# USB_BREAKOUTS_CCU_HAS.net
KiCad netlist of a schematic drawn in Altium Designer
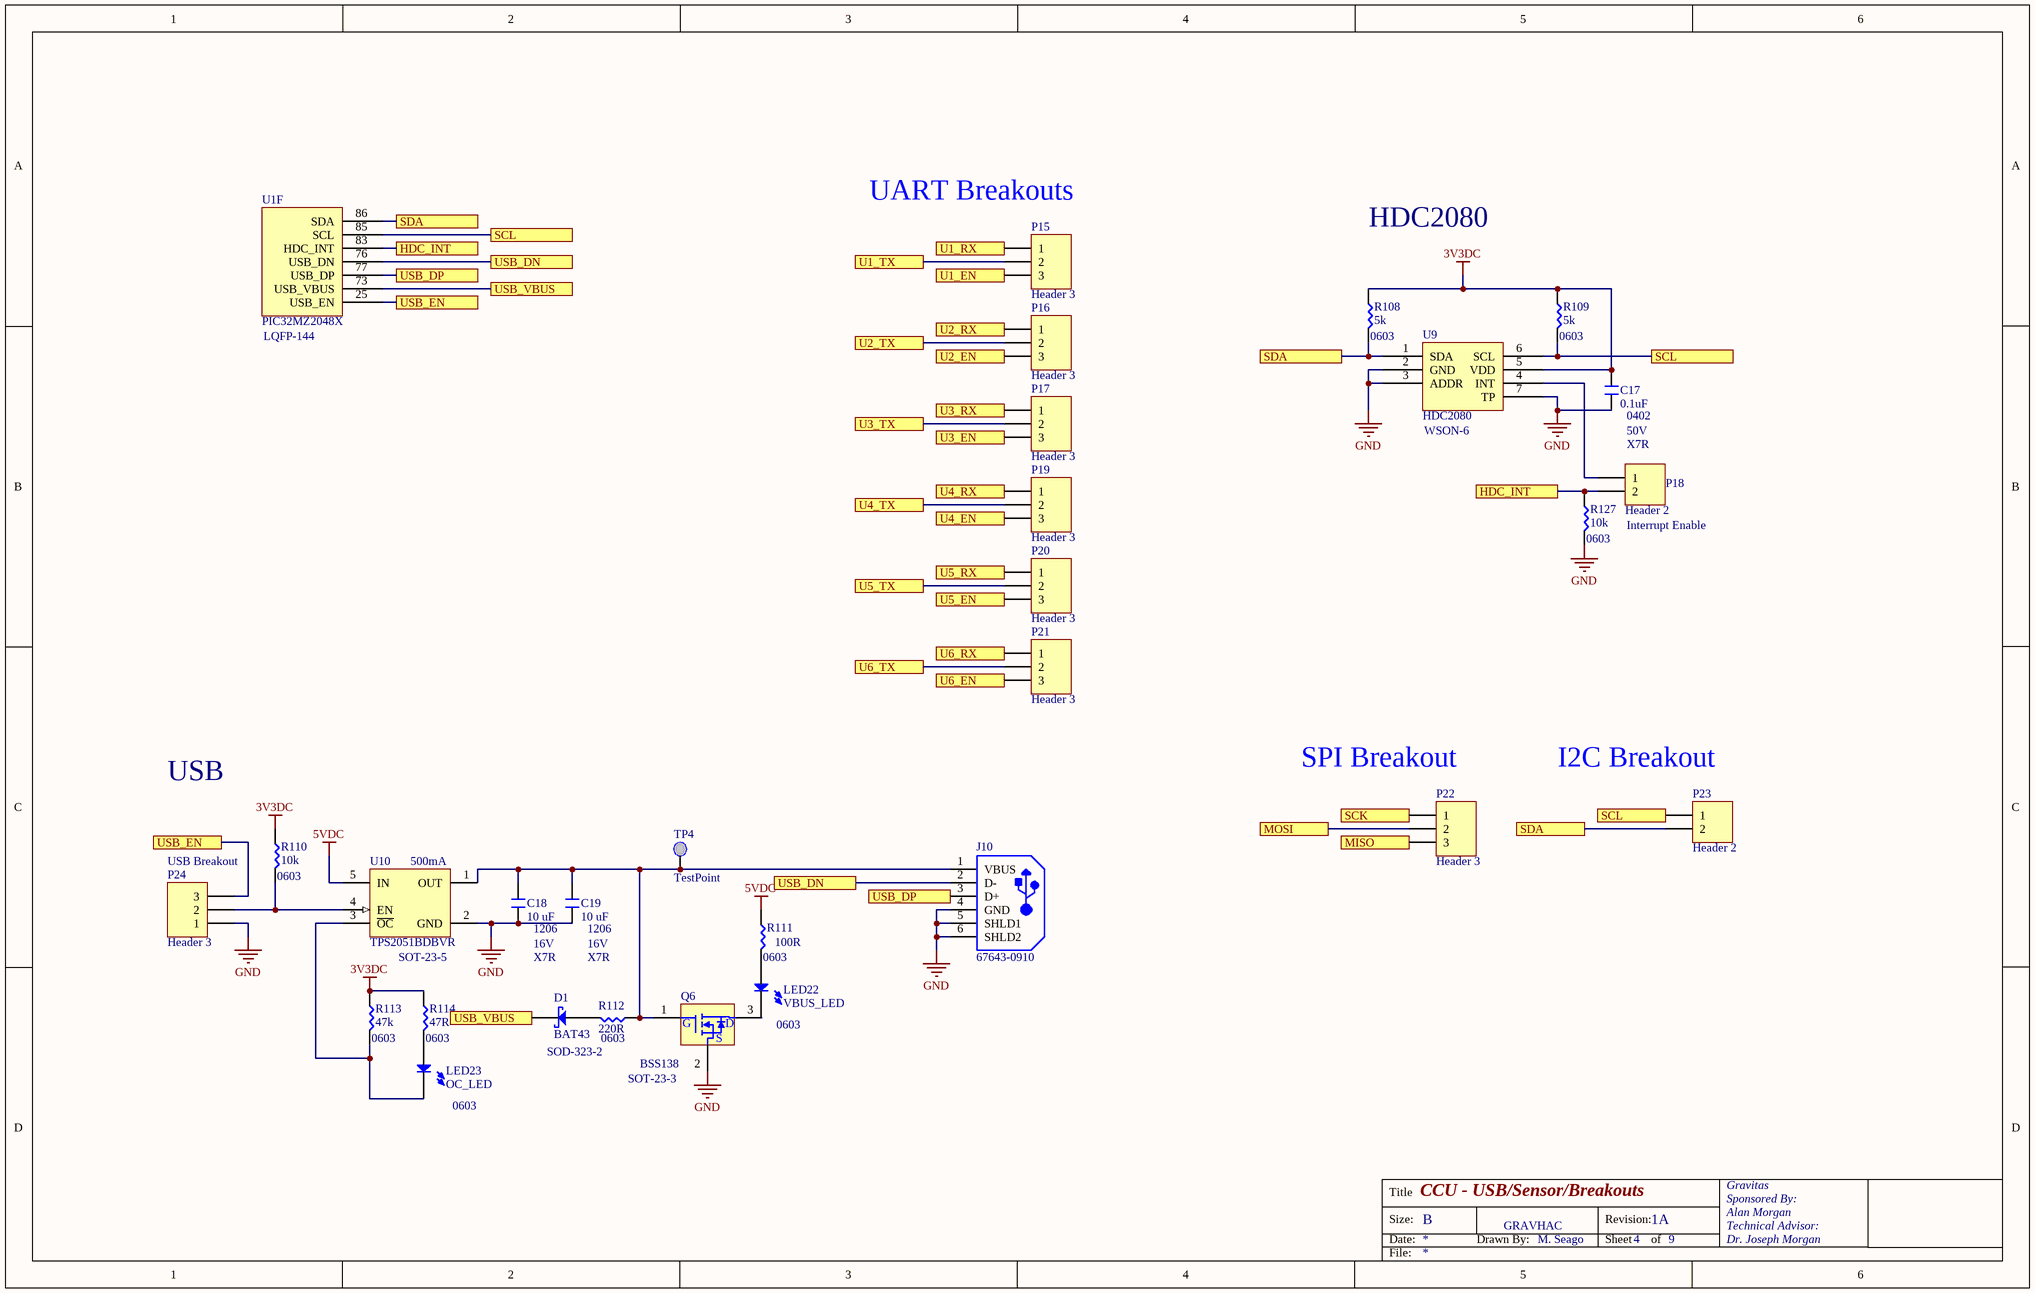
[diagram p0: USB_BREAKOUTS_CCU_HAS.SchDoc]

(export (version "E")
  (design (tool "Eeschema 10.0.6"))
  (components
    (comp (ref "C17")
      (value "0.1uF")
      (footprint "NonPolar-0402")
      (libsource (lib "GravLib") (part "Cap - 0402"))
    )
    (comp (ref "C18")
      (value "10 uF")
      (footprint "NONPOLAR-1206")
      (description "CGA5L1X7R1E106K160AE")
      (libsource (lib "GravLib") (part "Cap - 1206"))
    )
    (comp (ref "C19")
      (value "10 uF")
      (footprint "NONPOLAR-1206")
      (description "CGA5L1X7R1E106K160AE")
      (libsource (lib "GravLib") (part "Cap - 1206"))
    )
    (comp (ref "D1")
      (value "BAT43")
      (footprint "BAT43WS-E3-08")
      (description "BAT43WS-E3-08")
      (libsource (lib "GravLib") (part "BAT43"))
    )
    (comp (ref "J10")
      (value "67643-0910")
      (footprint "TE-292303-1_V")
      (fields (field (name "MANUFACTURER") "TE Connectivity"))
      (libsource (lib "Altium Content Vault") (part "USB-4-2SHLD"))
    )
    (comp (ref "LED22")
      (value "VBUS_LED")
      (footprint "LED-0603")
      (libsource (lib "GravLib") (part "LED-0603"))
    )
    (comp (ref "LED23") (value "OC_LED") (footprint "LED-0603") (libsource (lib "GravLib") (part "LED-0603")))
    (comp (ref "P15")
      (value "Header 3")
      (footprint "HDR1X3")
      (description "Header, 3-Pin")
      (fields (field (name "PUBLISHER") "Altium Limited"))
      (libsource (lib "Miscellaneous Connectors") (part "Header 3"))
    )
    (comp (ref "P16")
      (value "Header 3")
      (footprint "HDR1X3")
      (description "Header, 3-Pin")
      (fields (field (name "PUBLISHER") "Altium Limited"))
      (libsource (lib "Miscellaneous Connectors") (part "Header 3"))
    )
    (comp (ref "P17")
      (value "Header 3")
      (footprint "HDR1X3")
      (description "Header, 3-Pin")
      (fields (field (name "PUBLISHER") "Altium Limited"))
      (libsource (lib "Miscellaneous Connectors") (part "Header 3"))
    )
    (comp (ref "P18")
      (value "Header 2")
      (footprint "HDR1X2")
      (description "Header, 2-Pin")
      (fields (field (name "PUBLISHER") "Altium Limited"))
      (libsource (lib "Miscellaneous Connectors") (part "Header 2"))
    )
    (comp (ref "P19")
      (value "Header 3")
      (footprint "HDR1X3")
      (description "Header, 3-Pin")
      (fields (field (name "PUBLISHER") "Altium Limited"))
      (libsource (lib "Miscellaneous Connectors") (part "Header 3"))
    )
    (comp (ref "P20")
      (value "Header 3")
      (footprint "HDR1X3")
      (description "Header, 3-Pin")
      (fields (field (name "PUBLISHER") "Altium Limited"))
      (libsource (lib "Miscellaneous Connectors") (part "Header 3"))
    )
    (comp (ref "P21")
      (value "Header 3")
      (footprint "HDR1X3")
      (description "Header, 3-Pin")
      (fields (field (name "PUBLISHER") "Altium Limited"))
      (libsource (lib "Miscellaneous Connectors") (part "Header 3"))
    )
    (comp (ref "P22")
      (value "Header 3")
      (footprint "HDR1X3")
      (description "Header, 3-Pin")
      (fields (field (name "PUBLISHER") "Altium Limited"))
      (libsource (lib "Miscellaneous Connectors") (part "Header 3"))
    )
    (comp (ref "P23")
      (value "Header 2")
      (footprint "HDR1X2")
      (description "Header, 2-Pin")
      (fields (field (name "PUBLISHER") "Altium Limited"))
      (libsource (lib "Miscellaneous Connectors") (part "Header 2"))
    )
    (comp (ref "P24")
      (value "Header 3")
      (footprint "HDR1X3")
      (description "Header, 3-Pin")
      (fields (field (name "PUBLISHER") "Altium Limited"))
      (libsource (lib "") (part "Header 3_1"))
    )
    (comp (ref "Q6") (value "BSS138") (footprint "BSS138-SOT23") (libsource (lib "GravLib") (part "BSS138")))
    (comp (ref "R108")
      (value "5k")
      (footprint "NonPolar-0603")
      (libsource (lib "GravLib") (part "Res - 0603"))
    )
    (comp (ref "R109")
      (value "5k")
      (footprint "NonPolar-0603")
      (libsource (lib "GravLib") (part "Res - 0603"))
    )
    (comp (ref "R110")
      (value "10k")
      (footprint "NonPolar-0603")
      (libsource (lib "GravLib") (part "Res - 0603"))
    )
    (comp (ref "R111")
      (value "100R")
      (footprint "NonPolar-0603")
      (libsource (lib "GravLib") (part "Res - 0603"))
    )
    (comp (ref "R112")
      (value "220R")
      (footprint "NonPolar-0603")
      (libsource (lib "GravLib") (part "Res - 0603"))
    )
    (comp (ref "R113")
      (value "47k")
      (footprint "NonPolar-0603")
      (libsource (lib "GravLib") (part "Res - 0603"))
    )
    (comp (ref "R114")
      (value "47R")
      (footprint "NonPolar-0603")
      (libsource (lib "GravLib") (part "Res - 0603"))
    )
    (comp (ref "R127")
      (value "10k")
      (footprint "NonPolar-0603")
      (libsource (lib "GravLib") (part "Res - 0603"))
    )
    (comp (ref "TP4")
      (value "TestPoint")
      (footprint "TP - S2751-46R")
      (description "S2751-46R")
      (libsource (lib "GravLib") (part "TestPoint"))
    )
    (comp (ref "U1")
      (value "PIC32MZ2048X")
      (footprint "BIG_PIC32MZ")
      (libsource (lib "GravLib") (part "PIC32MZ2048X"))
    )
    (comp (ref "U9") (value "HDC2080") (footprint "HDC2080") (libsource (lib "GravLib") (part "HDC2080")))
    (comp (ref "U10")
      (value "TPS2051BDBVR")
      (footprint "DBV0005A_L")
      (fields (field (name "MANUFACTURER") "TexasInstruments"))
      (libsource (lib "Altium Content Vault") (part "TI-TPS2051BDBV5"))
    )
  )
  (nets
    (net (code "1") (name "/HDC_INT") (class "Default")
      (node (ref "P18") (pin "2") (pinfunction "2_2") (pintype "passive"))
      (node (ref "R127") (pin "2") (pinfunction "2_2") (pintype "passive"))
      (node (ref "U1") (pin "83") (pinfunction "HDC_INT_83") (pintype "passive"))
    )
    (net (code "2") (name "/MISO") (class "Default")
      (node (ref "P22") (pin "3") (pinfunction "3_3") (pintype "passive"))
    )
    (net (code "3") (name "/MOSI") (class "Default")
      (node (ref "P22") (pin "2") (pinfunction "2_2") (pintype "passive"))
    )
    (net (code "4") (name "/SCK") (class "Default")
      (node (ref "P22") (pin "1") (pinfunction "1_1") (pintype "passive"))
    )
    (net (code "5") (name "/SCL") (class "Default")
      (node (ref "P23") (pin "1") (pinfunction "1_1") (pintype "passive"))
      (node (ref "R109") (pin "1") (pinfunction "1_1") (pintype "passive"))
      (node (ref "U1") (pin "85") (pinfunction "SCL_85") (pintype "passive"))
      (node (ref "U9") (pin "6") (pinfunction "SCL_6") (pintype "passive"))
    )
    (net (code "6") (name "/SDA") (class "Default")
      (node (ref "P23") (pin "2") (pinfunction "2_2") (pintype "passive"))
      (node (ref "R108") (pin "1") (pinfunction "1_1") (pintype "passive"))
      (node (ref "U1") (pin "86") (pinfunction "SDA_86") (pintype "passive"))
      (node (ref "U9") (pin "1") (pinfunction "SDA_1") (pintype "passive"))
    )
    (net (code "7") (name "/U1_EN") (class "Default")
      (node (ref "P15") (pin "3") (pinfunction "3_3") (pintype "passive"))
    )
    (net (code "8") (name "/U1_RX") (class "Default")
      (node (ref "P15") (pin "1") (pinfunction "1_1") (pintype "passive"))
    )
    (net (code "9") (name "/U1_TX") (class "Default")
      (node (ref "P15") (pin "2") (pinfunction "2_2") (pintype "passive"))
    )
    (net (code "10") (name "/U2_EN") (class "Default")
      (node (ref "P16") (pin "3") (pinfunction "3_3") (pintype "passive"))
    )
    (net (code "11") (name "/U2_RX") (class "Default")
      (node (ref "P16") (pin "1") (pinfunction "1_1") (pintype "passive"))
    )
    (net (code "12") (name "/U2_TX") (class "Default")
      (node (ref "P16") (pin "2") (pinfunction "2_2") (pintype "passive"))
    )
    (net (code "13") (name "/U3_EN") (class "Default")
      (node (ref "P17") (pin "3") (pinfunction "3_3") (pintype "passive"))
    )
    (net (code "14") (name "/U3_RX") (class "Default")
      (node (ref "P17") (pin "1") (pinfunction "1_1") (pintype "passive"))
    )
    (net (code "15") (name "/U3_TX") (class "Default")
      (node (ref "P17") (pin "2") (pinfunction "2_2") (pintype "passive"))
    )
    (net (code "16") (name "/U4_EN") (class "Default")
      (node (ref "P19") (pin "3") (pinfunction "3_3") (pintype "passive"))
    )
    (net (code "17") (name "/U4_RX") (class "Default")
      (node (ref "P19") (pin "1") (pinfunction "1_1") (pintype "passive"))
    )
    (net (code "18") (name "/U4_TX") (class "Default")
      (node (ref "P19") (pin "2") (pinfunction "2_2") (pintype "passive"))
    )
    (net (code "19") (name "/U5_EN") (class "Default")
      (node (ref "P20") (pin "3") (pinfunction "3_3") (pintype "passive"))
    )
    (net (code "20") (name "/U5_RX") (class "Default")
      (node (ref "P20") (pin "1") (pinfunction "1_1") (pintype "passive"))
    )
    (net (code "21") (name "/U5_TX") (class "Default")
      (node (ref "P20") (pin "2") (pinfunction "2_2") (pintype "passive"))
    )
    (net (code "22") (name "/U6_EN") (class "Default")
      (node (ref "P21") (pin "3") (pinfunction "3_3") (pintype "passive"))
    )
    (net (code "23") (name "/U6_RX") (class "Default")
      (node (ref "P21") (pin "1") (pinfunction "1_1") (pintype "passive"))
    )
    (net (code "24") (name "/U6_TX") (class "Default")
      (node (ref "P21") (pin "2") (pinfunction "2_2") (pintype "passive"))
    )
    (net (code "25") (name "/USB_DN") (class "Default")
      (node (ref "J10") (pin "2") (pinfunction "D-_2") (pintype "passive"))
      (node (ref "U1") (pin "76") (pinfunction "USB_DN_76") (pintype "passive"))
    )
    (net (code "26") (name "/USB_DP") (class "Default")
      (node (ref "J10") (pin "3") (pinfunction "D+_3") (pintype "passive"))
      (node (ref "U1") (pin "77") (pinfunction "USB_DP_77") (pintype "passive"))
    )
    (net (code "27") (name "/USB_EN") (class "Default")
      (node (ref "P24") (pin "3") (pinfunction "3_3") (pintype "passive"))
      (node (ref "U1") (pin "25") (pinfunction "USB_EN_25") (pintype "passive"))
    )
    (net (code "28") (name "/USB_VBUS") (class "Default")
      (node (ref "D1") (pin "1") (pinfunction "1_1") (pintype "passive"))
      (node (ref "U1") (pin "73") (pinfunction "USB_VBUS_73") (pintype "passive"))
    )
    (net (code "29") (name "3V3DC") (class "Default")
      (node (ref "C17") (pin "2") (pinfunction "2_2") (pintype "passive"))
      (node (ref "R108") (pin "2") (pinfunction "2_2") (pintype "passive"))
      (node (ref "R109") (pin "2") (pinfunction "2_2") (pintype "passive"))
      (node (ref "R110") (pin "2") (pinfunction "2_2") (pintype "passive"))
      (node (ref "R113") (pin "2") (pinfunction "2_2") (pintype "passive"))
      (node (ref "R114") (pin "2") (pinfunction "2_2") (pintype "passive"))
      (node (ref "U9") (pin "5") (pinfunction "VDD_5") (pintype "passive"))
    )
    (net (code "30") (name "5VDC") (class "Default")
      (node (ref "R111") (pin "2") (pinfunction "2_2") (pintype "passive"))
      (node (ref "U10") (pin "5") (pinfunction "IN_5") (pintype "power_in"))
    )
    (net (code "31") (name "GND") (class "Default")
      (node (ref "C17") (pin "1") (pinfunction "1_1") (pintype "passive"))
      (node (ref "C18") (pin "1") (pinfunction "1_1") (pintype "passive"))
      (node (ref "C19") (pin "1") (pinfunction "1_1") (pintype "passive"))
      (node (ref "J10") (pin "4") (pinfunction "GND_4") (pintype "passive"))
      (node (ref "J10") (pin "5") (pinfunction "SHLD1_5") (pintype "passive"))
      (node (ref "J10") (pin "6") (pinfunction "SHLD2_6") (pintype "passive"))
      (node (ref "P24") (pin "1") (pinfunction "1_1") (pintype "passive"))
      (node (ref "Q6") (pin "2") (pinfunction "S_2") (pintype "passive"))
      (node (ref "R127") (pin "1") (pinfunction "1_1") (pintype "passive"))
      (node (ref "U10") (pin "2") (pinfunction "GND_2") (pintype "power_in"))
      (node (ref "U9") (pin "2") (pinfunction "GND_2") (pintype "passive"))
      (node (ref "U9") (pin "3") (pinfunction "ADDR_3") (pintype "passive"))
      (node (ref "U9") (pin "7") (pinfunction "TP_7") (pintype "passive"))
    )
    (net (code "32") (name "Net-(D1-Pad2)") (class "Default")
      (node (ref "D1") (pin "2") (pinfunction "2_2") (pintype "passive"))
      (node (ref "R112") (pin "1") (pinfunction "1_1") (pintype "passive"))
    )
    (net (code "33") (name "Net-(J10-VBUS)") (class "Default")
      (node (ref "C18") (pin "2") (pinfunction "2_2") (pintype "passive"))
      (node (ref "C19") (pin "2") (pinfunction "2_2") (pintype "passive"))
      (node (ref "J10") (pin "1") (pinfunction "VBUS_1") (pintype "passive"))
      (node (ref "Q6") (pin "1") (pinfunction "G_1") (pintype "passive"))
      (node (ref "R112") (pin "2") (pinfunction "2_2") (pintype "passive"))
      (node (ref "TP4") (pin "1") (pinfunction "1_1") (pintype "passive"))
      (node (ref "U10") (pin "1") (pinfunction "OUT_1") (pintype "power_in"))
    )
    (net (code "34") (name "Net-(LED22-Pad1)") (class "Default")
      (node (ref "LED22") (pin "1") (pinfunction "1_1") (pintype "passive"))
      (node (ref "R111") (pin "1") (pinfunction "1_1") (pintype "passive"))
    )
    (net (code "35") (name "Net-(LED23-Pad1)") (class "Default")
      (node (ref "LED23") (pin "1") (pinfunction "1_1") (pintype "passive"))
      (node (ref "R114") (pin "1") (pinfunction "1_1") (pintype "passive"))
    )
    (net (code "36") (name "Net-(Q6-D)") (class "Default")
      (node (ref "LED22") (pin "2") (pinfunction "2_2") (pintype "passive"))
      (node (ref "Q6") (pin "3") (pinfunction "D_3") (pintype "passive"))
    )
    (net (code "37") (name "Net-(U9-INT)") (class "Default")
      (node (ref "P18") (pin "1") (pinfunction "1_1") (pintype "passive"))
      (node (ref "U9") (pin "4") (pinfunction "INT_4") (pintype "passive"))
    )
    (net (code "38") (name "Net-(U10-EN)") (class "Default")
      (node (ref "P24") (pin "2") (pinfunction "2_2") (pintype "passive"))
      (node (ref "R110") (pin "1") (pinfunction "1_1") (pintype "passive"))
      (node (ref "U10") (pin "4") (pinfunction "EN_4") (pintype "input"))
    )
    (net (code "39") (name "Net-(U10-~{OC})") (class "Default")
      (node (ref "LED23") (pin "2") (pinfunction "2_2") (pintype "passive"))
      (node (ref "R113") (pin "1") (pinfunction "1_1") (pintype "passive"))
      (node (ref "U10") (pin "3") (pinfunction "~{OC}_3") (pintype "open_collector"))
    )
  )
)
